# adc_40MHz_v3.net
KiCad netlist of a schematic drawn in EAGLE
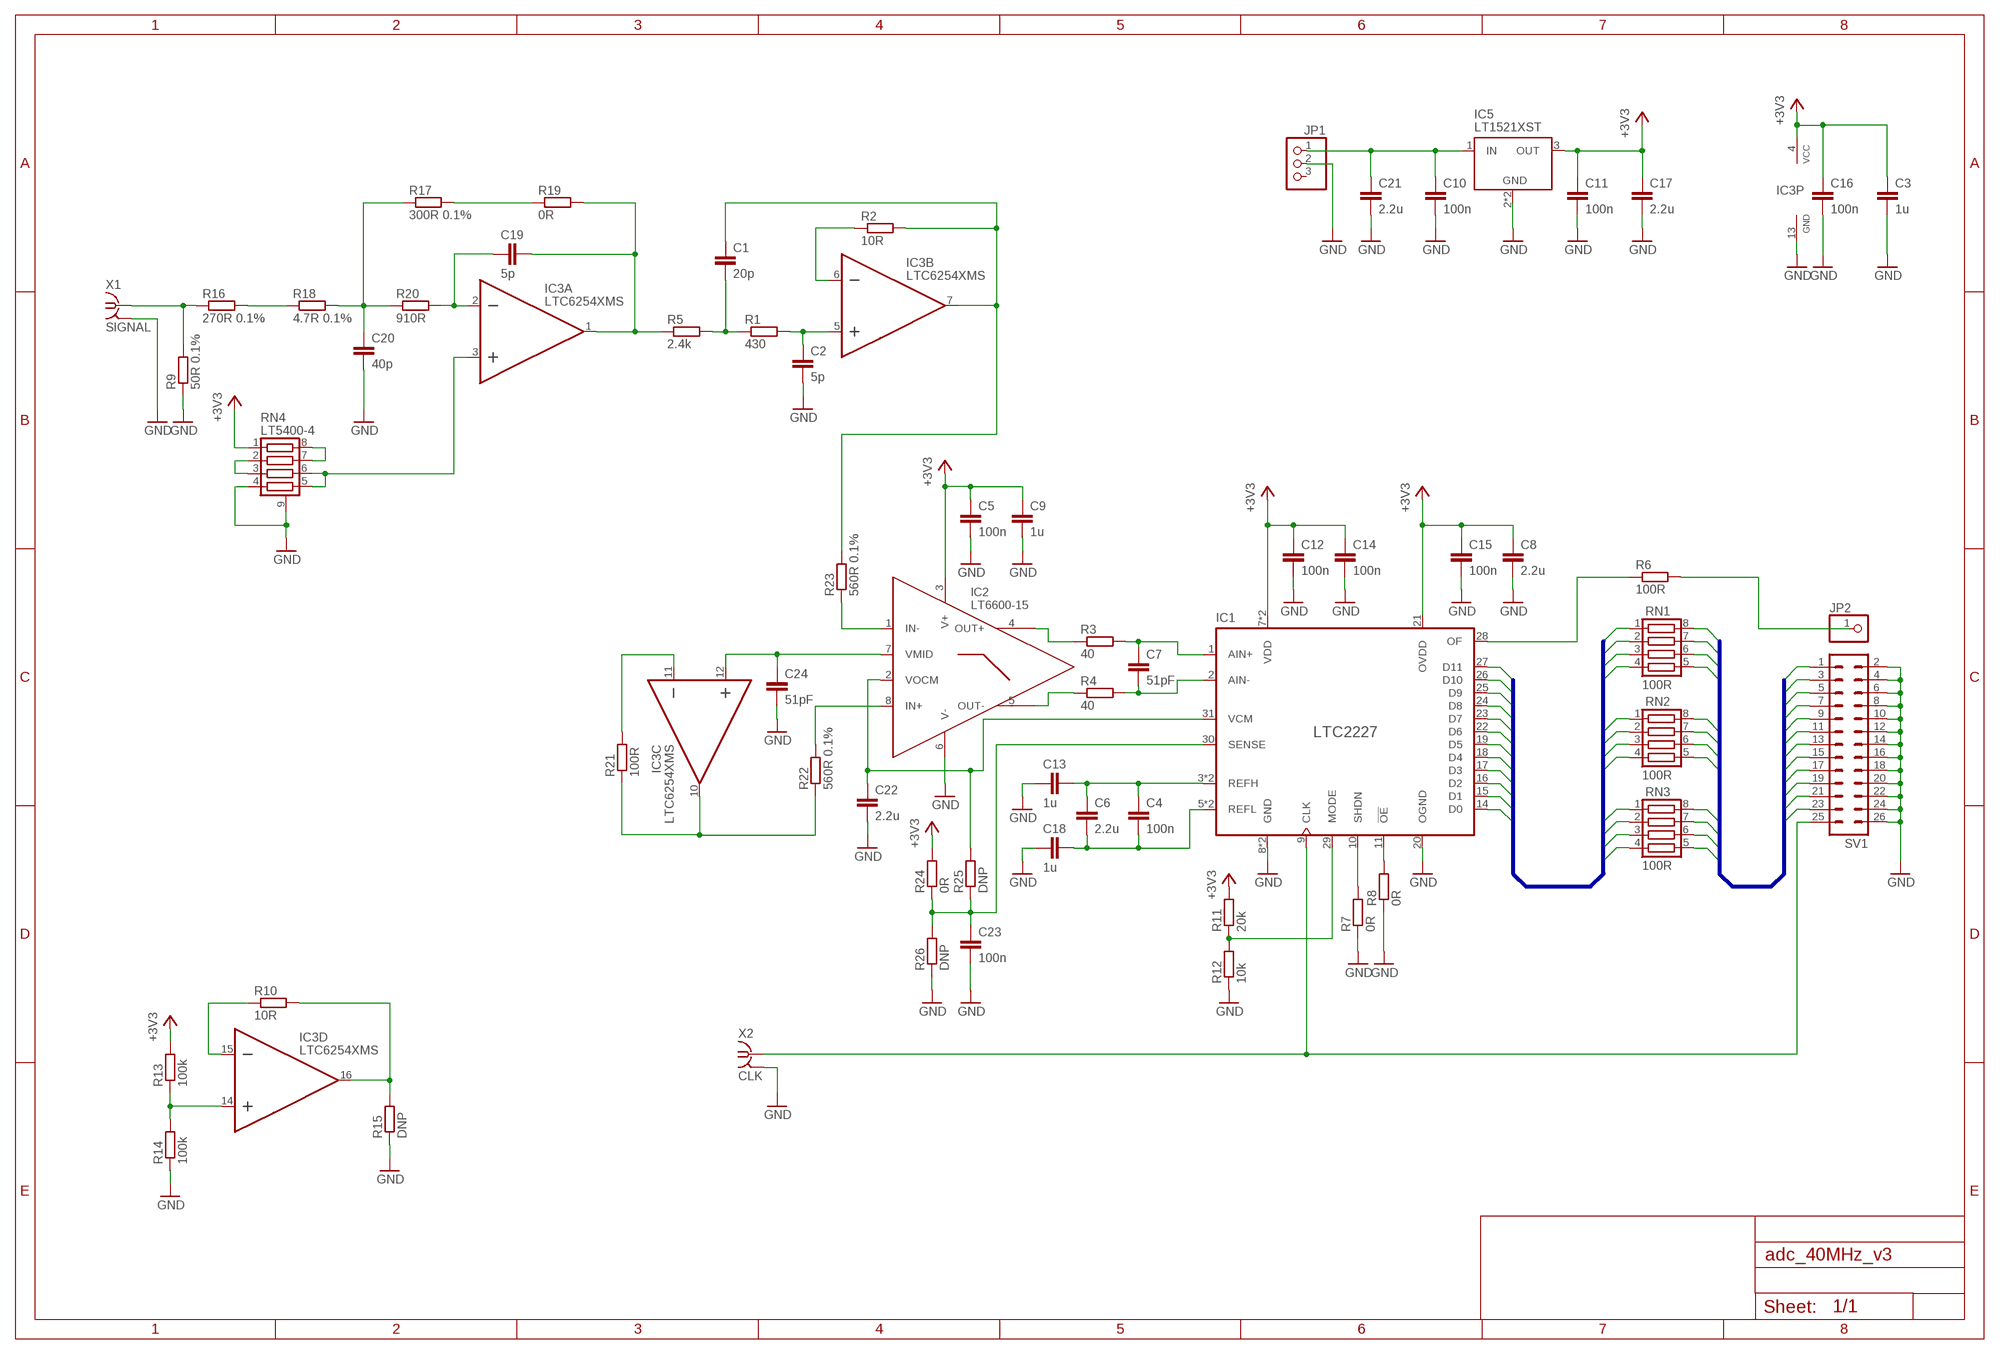
[diagram p0: schematic, sheet 1]

(export (version "E")
  (design (tool "Eeschema 10.0.6"))
  (components
    (comp (ref "C1")
      (value "20p")
      (footprint "eagle-import:C0603")
      (libsource (lib "eagle-import") (part "C-EUC0603"))
    )
    (comp (ref "C2")
      (value "5p")
      (footprint "eagle-import:C0603")
      (libsource (lib "eagle-import") (part "C-EUC0603"))
    )
    (comp (ref "C3")
      (value "1u")
      (footprint "eagle-import:C0805")
      (libsource (lib "eagle-import") (part "C-EUC0805"))
    )
    (comp (ref "C4")
      (value "100n")
      (footprint "eagle-import:C0603")
      (libsource (lib "eagle-import") (part "C-EUC0603"))
    )
    (comp (ref "C5")
      (value "100n")
      (footprint "eagle-import:C0603")
      (libsource (lib "eagle-import") (part "C-EUC0603"))
    )
    (comp (ref "C6")
      (value "2.2u")
      (footprint "eagle-import:C0805")
      (libsource (lib "eagle-import") (part "C-EUC0805"))
    )
    (comp (ref "C7")
      (value "51pF")
      (footprint "eagle-import:C0603")
      (libsource (lib "eagle-import") (part "C-EUC0603"))
    )
    (comp (ref "C8")
      (value "2.2u")
      (footprint "eagle-import:C0805")
      (libsource (lib "eagle-import") (part "C-EUC0805"))
    )
    (comp (ref "C9")
      (value "1u")
      (footprint "eagle-import:C0805")
      (libsource (lib "eagle-import") (part "C-EUC0805"))
    )
    (comp (ref "C10")
      (value "100n")
      (footprint "eagle-import:C0805")
      (libsource (lib "eagle-import") (part "C-EUC0805"))
    )
    (comp (ref "C11")
      (value "100n")
      (footprint "eagle-import:C0805")
      (libsource (lib "eagle-import") (part "C-EUC0805"))
    )
    (comp (ref "C12")
      (value "100n")
      (footprint "eagle-import:C0603")
      (libsource (lib "eagle-import") (part "C-EUC0603"))
    )
    (comp (ref "C13")
      (value "1u")
      (footprint "eagle-import:C0805")
      (libsource (lib "eagle-import") (part "C-EUC0805"))
    )
    (comp (ref "C14")
      (value "100n")
      (footprint "eagle-import:C0603")
      (libsource (lib "eagle-import") (part "C-EUC0603"))
    )
    (comp (ref "C15")
      (value "100n")
      (footprint "eagle-import:C0603")
      (libsource (lib "eagle-import") (part "C-EUC0603"))
    )
    (comp (ref "C16")
      (value "100n")
      (footprint "eagle-import:C0805")
      (libsource (lib "eagle-import") (part "C-EUC0805"))
    )
    (comp (ref "C17")
      (value "2.2u")
      (footprint "eagle-import:C0805")
      (libsource (lib "eagle-import") (part "C-EUC0805"))
    )
    (comp (ref "C18")
      (value "1u")
      (footprint "eagle-import:C0805")
      (libsource (lib "eagle-import") (part "C-EUC0805"))
    )
    (comp (ref "C19")
      (value "5p")
      (footprint "eagle-import:C0603")
      (libsource (lib "eagle-import") (part "C-EUC0603"))
    )
    (comp (ref "C20")
      (value "40p")
      (footprint "eagle-import:C0603")
      (libsource (lib "eagle-import") (part "C-EUC0603"))
    )
    (comp (ref "C21")
      (value "2.2u")
      (footprint "eagle-import:C0805")
      (libsource (lib "eagle-import") (part "C-EUC0805"))
    )
    (comp (ref "C22")
      (value "2.2u")
      (footprint "eagle-import:C0805")
      (libsource (lib "eagle-import") (part "C-EUC0805"))
    )
    (comp (ref "C23")
      (value "100n")
      (footprint "eagle-import:C0603")
      (libsource (lib "eagle-import") (part "C-EUC0603"))
    )
    (comp (ref "C24")
      (value "51pF")
      (footprint "eagle-import:C0603")
      (libsource (lib "eagle-import") (part "C-EUC0603"))
    )
    (comp (ref "IC1")
      (value "LTC2227")
      (footprint "eagle-import:QFN32")
      (libsource (lib "eagle-import") (part "LTC2227"))
    )
    (comp (ref "IC2")
      (value "LT6600-15")
      (footprint "eagle-import:S8")
      (libsource (lib "eagle-import") (part "LT6600-15"))
    )
    (comp (ref "IC3")
      (value "LTC6254XMS")
      (footprint "eagle-import:MSOP16")
      (libsource (lib "eagle-import") (part "LTC6254XMS"))
    )
    (comp (ref "IC5")
      (value "LT1521XST")
      (footprint "eagle-import:SOT223")
      (libsource (lib "eagle-import") (part "LT1521XST"))
    )
    (comp (ref "JP1")
      (value "PINHD-1X3/90")
      (footprint "eagle-import:1X03_90")
      (libsource (lib "eagle-import") (part "PINHD-1X3/90"))
    )
    (comp (ref "JP2")
      (value "PINHD-1X1")
      (footprint "eagle-import:1X01")
      (libsource (lib "eagle-import") (part "PINHD-1X1"))
    )
    (comp (ref "R1")
      (value "430")
      (footprint "eagle-import:R0603")
      (libsource (lib "eagle-import") (part "R-EU_R0603"))
    )
    (comp (ref "R2")
      (value "10R")
      (footprint "eagle-import:R0603")
      (libsource (lib "eagle-import") (part "R-EU_R0603"))
    )
    (comp (ref "R3")
      (value "40")
      (footprint "eagle-import:R0603")
      (libsource (lib "eagle-import") (part "R-EU_R0603"))
    )
    (comp (ref "R4")
      (value "40")
      (footprint "eagle-import:R0603")
      (libsource (lib "eagle-import") (part "R-EU_R0603"))
    )
    (comp (ref "R5")
      (value "2.4k")
      (footprint "eagle-import:R0603")
      (libsource (lib "eagle-import") (part "R-EU_R0603"))
    )
    (comp (ref "R6")
      (value "100R")
      (footprint "eagle-import:R0603")
      (libsource (lib "eagle-import") (part "R-EU_R0603"))
    )
    (comp (ref "R7")
      (value "0R")
      (footprint "eagle-import:R0603")
      (libsource (lib "eagle-import") (part "R-EU_R0603"))
    )
    (comp (ref "R8")
      (value "0R")
      (footprint "eagle-import:R0603")
      (libsource (lib "eagle-import") (part "R-EU_R0603"))
    )
    (comp (ref "R9")
      (value "50R 0.1%")
      (footprint "eagle-import:R0603")
      (libsource (lib "eagle-import") (part "R-EU_R0603"))
    )
    (comp (ref "R10")
      (value "10R")
      (footprint "eagle-import:R0603")
      (libsource (lib "eagle-import") (part "R-EU_R0603"))
    )
    (comp (ref "R11")
      (value "20k")
      (footprint "eagle-import:R0603")
      (libsource (lib "eagle-import") (part "R-EU_R0603"))
    )
    (comp (ref "R12")
      (value "10k")
      (footprint "eagle-import:R0603")
      (libsource (lib "eagle-import") (part "R-EU_R0603"))
    )
    (comp (ref "R13")
      (value "100k")
      (footprint "eagle-import:R0603")
      (libsource (lib "eagle-import") (part "R-EU_R0603"))
    )
    (comp (ref "R14")
      (value "100k")
      (footprint "eagle-import:R0603")
      (libsource (lib "eagle-import") (part "R-EU_R0603"))
    )
    (comp (ref "R15")
      (value "DNP")
      (footprint "eagle-import:R0603")
      (libsource (lib "eagle-import") (part "R-EU_R0603"))
    )
    (comp (ref "R16")
      (value "270R 0.1%")
      (footprint "eagle-import:R0603")
      (libsource (lib "eagle-import") (part "R-EU_R0603"))
    )
    (comp (ref "R17")
      (value "300R 0.1%")
      (footprint "eagle-import:R0603")
      (libsource (lib "eagle-import") (part "R-EU_R0603"))
    )
    (comp (ref "R18")
      (value "4.7R 0.1%")
      (footprint "eagle-import:R0603")
      (libsource (lib "eagle-import") (part "R-EU_R0603"))
    )
    (comp (ref "R19")
      (value "0R")
      (footprint "eagle-import:R0603")
      (libsource (lib "eagle-import") (part "R-EU_R0603"))
    )
    (comp (ref "R20")
      (value "910R")
      (footprint "eagle-import:R0603")
      (libsource (lib "eagle-import") (part "R-EU_R0603"))
    )
    (comp (ref "R21")
      (value "100R")
      (footprint "eagle-import:R0603")
      (libsource (lib "eagle-import") (part "R-EU_R0603"))
    )
    (comp (ref "R22")
      (value "560R 0.1%")
      (footprint "eagle-import:R0603")
      (libsource (lib "eagle-import") (part "R-EU_R0603"))
    )
    (comp (ref "R23")
      (value "560R 0.1%")
      (footprint "eagle-import:R0603")
      (libsource (lib "eagle-import") (part "R-EU_R0603"))
    )
    (comp (ref "R24")
      (value "0R")
      (footprint "eagle-import:R0603")
      (libsource (lib "eagle-import") (part "R-EU_R0603"))
    )
    (comp (ref "R25")
      (value "DNP")
      (footprint "eagle-import:R0603")
      (libsource (lib "eagle-import") (part "R-EU_R0603"))
    )
    (comp (ref "R26")
      (value "DNP")
      (footprint "eagle-import:R0603")
      (libsource (lib "eagle-import") (part "R-EU_R0603"))
    )
    (comp (ref "RN1")
      (value "100R")
      (footprint "eagle-import:EXB38V")
      (libsource (lib "eagle-import") (part "CTS742C083"))
    )
    (comp (ref "RN2")
      (value "100R")
      (footprint "eagle-import:EXB38V")
      (libsource (lib "eagle-import") (part "CTS742C083"))
    )
    (comp (ref "RN3")
      (value "100R")
      (footprint "eagle-import:EXB38V")
      (libsource (lib "eagle-import") (part "CTS742C083"))
    )
    (comp (ref "RN4")
      (value "LT5400-4")
      (footprint "eagle-import:MS8E")
      (libsource (lib "eagle-import") (part "LT5400"))
    )
    (comp (ref "SV1")
      (value "ML26")
      (footprint "eagle-import:ML26")
      (libsource (lib "eagle-import") (part "ML26"))
    )
    (comp (ref "X1")
      (value "SIGNAL")
      (footprint "eagle-import:BU-SMA-H")
      (libsource (lib "eagle-import") (part "BU-SMA-H"))
    )
    (comp (ref "X2")
      (value "CLK")
      (footprint "eagle-import:BU-SMA-H")
      (libsource (lib "eagle-import") (part "BU-SMA-H"))
    )
  )
  (nets
    (net (code "1") (name "+3V3") (class "Default")
      (node (ref "C11") (pin "1") (pinfunction "1_1") (pintype "passive"))
      (node (ref "C12") (pin "1") (pinfunction "1_1") (pintype "passive"))
      (node (ref "C14") (pin "1") (pinfunction "1_1") (pintype "passive"))
      (node (ref "C15") (pin "1") (pinfunction "1_1") (pintype "passive"))
      (node (ref "C16") (pin "1") (pinfunction "1_1") (pintype "passive"))
      (node (ref "C17") (pin "1") (pinfunction "1_1") (pintype "passive"))
      (node (ref "C3") (pin "1") (pinfunction "1_1") (pintype "passive"))
      (node (ref "C5") (pin "1") (pinfunction "1_1") (pintype "passive"))
      (node (ref "C8") (pin "1") (pinfunction "1_1") (pintype "passive"))
      (node (ref "C9") (pin "1") (pinfunction "1_1") (pintype "passive"))
      (node (ref "IC1") (pin "21") (pinfunction "OVDD_21") (pintype "power_in"))
      (node (ref "IC1") (pin "32") (pinfunction "VDD_32") (pintype "power_in"))
      (node (ref "IC1") (pin "7") (pinfunction "VDD_7") (pintype "power_in"))
      (node (ref "IC2") (pin "3") (pinfunction "V+_3") (pintype "power_in"))
      (node (ref "IC3") (pin "4") (pinfunction "V+_4") (pintype "power_in"))
      (node (ref "IC5") (pin "3") (pinfunction "OUT_3") (pintype "output"))
      (node (ref "R11") (pin "2") (pinfunction "2_2") (pintype "passive"))
      (node (ref "R13") (pin "2") (pinfunction "2_2") (pintype "passive"))
      (node (ref "R24") (pin "2") (pinfunction "2_2") (pintype "passive"))
      (node (ref "RN4") (pin "1") (pinfunction "1_1") (pintype "passive"))
    )
    (net (code "2") (name "/ADC_D0") (class "Default")
      (node (ref "IC1") (pin "14") (pinfunction "D0_14") (pintype "output"))
      (node (ref "RN3") (pin "4") (pinfunction "4_4") (pintype "passive"))
    )
    (net (code "3") (name "/ADC_D1") (class "Default")
      (node (ref "IC1") (pin "15") (pinfunction "D1_15") (pintype "output"))
      (node (ref "RN3") (pin "3") (pinfunction "3_3") (pintype "passive"))
    )
    (net (code "4") (name "/ADC_D2") (class "Default")
      (node (ref "IC1") (pin "16") (pinfunction "D2_16") (pintype "output"))
      (node (ref "RN3") (pin "2") (pinfunction "2_2") (pintype "passive"))
    )
    (net (code "5") (name "/ADC_D3") (class "Default")
      (node (ref "IC1") (pin "17") (pinfunction "D3_17") (pintype "output"))
      (node (ref "RN3") (pin "1") (pinfunction "1_1") (pintype "passive"))
    )
    (net (code "6") (name "/ADC_D4") (class "Default")
      (node (ref "IC1") (pin "18") (pinfunction "D4_18") (pintype "output"))
      (node (ref "RN2") (pin "4") (pinfunction "4_4") (pintype "passive"))
    )
    (net (code "7") (name "/ADC_D5") (class "Default")
      (node (ref "IC1") (pin "19") (pinfunction "D5_19") (pintype "output"))
      (node (ref "RN2") (pin "3") (pinfunction "3_3") (pintype "passive"))
    )
    (net (code "8") (name "/ADC_D6") (class "Default")
      (node (ref "IC1") (pin "22") (pinfunction "D6_22") (pintype "output"))
      (node (ref "RN2") (pin "2") (pinfunction "2_2") (pintype "passive"))
    )
    (net (code "9") (name "/ADC_D7") (class "Default")
      (node (ref "IC1") (pin "23") (pinfunction "D7_23") (pintype "output"))
      (node (ref "RN2") (pin "1") (pinfunction "1_1") (pintype "passive"))
    )
    (net (code "10") (name "/ADC_D8") (class "Default")
      (node (ref "IC1") (pin "24") (pinfunction "D8_24") (pintype "output"))
      (node (ref "RN1") (pin "4") (pinfunction "4_4") (pintype "passive"))
    )
    (net (code "11") (name "/ADC_D9") (class "Default")
      (node (ref "IC1") (pin "25") (pinfunction "D9_25") (pintype "output"))
      (node (ref "RN1") (pin "3") (pinfunction "3_3") (pintype "passive"))
    )
    (net (code "12") (name "/ADC_D10") (class "Default")
      (node (ref "IC1") (pin "26") (pinfunction "D10_26") (pintype "output"))
      (node (ref "RN1") (pin "2") (pinfunction "2_2") (pintype "passive"))
    )
    (net (code "13") (name "/ADC_D11") (class "Default")
      (node (ref "IC1") (pin "27") (pinfunction "D11_27") (pintype "output"))
      (node (ref "RN1") (pin "1") (pinfunction "1_1") (pintype "passive"))
    )
    (net (code "14") (name "/DAC_D0") (class "Default")
      (node (ref "RN3") (pin "5") (pinfunction "5_5") (pintype "passive"))
      (node (ref "SV1") (pin "23") (pinfunction "23_23") (pintype "passive"))
    )
    (net (code "15") (name "/DAC_D1") (class "Default")
      (node (ref "RN3") (pin "6") (pinfunction "6_6") (pintype "passive"))
      (node (ref "SV1") (pin "21") (pinfunction "21_21") (pintype "passive"))
    )
    (net (code "16") (name "/DAC_D2") (class "Default")
      (node (ref "RN3") (pin "7") (pinfunction "7_7") (pintype "passive"))
      (node (ref "SV1") (pin "19") (pinfunction "19_19") (pintype "passive"))
    )
    (net (code "17") (name "/DAC_D3") (class "Default")
      (node (ref "RN3") (pin "8") (pinfunction "8_8") (pintype "passive"))
      (node (ref "SV1") (pin "17") (pinfunction "17_17") (pintype "passive"))
    )
    (net (code "18") (name "/DAC_D4") (class "Default")
      (node (ref "RN2") (pin "5") (pinfunction "5_5") (pintype "passive"))
      (node (ref "SV1") (pin "15") (pinfunction "15_15") (pintype "passive"))
    )
    (net (code "19") (name "/DAC_D5") (class "Default")
      (node (ref "RN2") (pin "6") (pinfunction "6_6") (pintype "passive"))
      (node (ref "SV1") (pin "13") (pinfunction "13_13") (pintype "passive"))
    )
    (net (code "20") (name "/DAC_D6") (class "Default")
      (node (ref "RN2") (pin "7") (pinfunction "7_7") (pintype "passive"))
      (node (ref "SV1") (pin "11") (pinfunction "11_11") (pintype "passive"))
    )
    (net (code "21") (name "/DAC_D7") (class "Default")
      (node (ref "RN2") (pin "8") (pinfunction "8_8") (pintype "passive"))
      (node (ref "SV1") (pin "9") (pinfunction "9_9") (pintype "passive"))
    )
    (net (code "22") (name "/DAC_D8") (class "Default")
      (node (ref "RN1") (pin "5") (pinfunction "5_5") (pintype "passive"))
      (node (ref "SV1") (pin "7") (pinfunction "7_7") (pintype "passive"))
    )
    (net (code "23") (name "/DAC_D9") (class "Default")
      (node (ref "RN1") (pin "6") (pinfunction "6_6") (pintype "passive"))
      (node (ref "SV1") (pin "5") (pinfunction "5_5") (pintype "passive"))
    )
    (net (code "24") (name "/DAC_D10") (class "Default")
      (node (ref "RN1") (pin "7") (pinfunction "7_7") (pintype "passive"))
      (node (ref "SV1") (pin "3") (pinfunction "3_3") (pintype "passive"))
    )
    (net (code "25") (name "/DAC_D11") (class "Default")
      (node (ref "RN1") (pin "8") (pinfunction "8_8") (pintype "passive"))
      (node (ref "SV1") (pin "1") (pinfunction "1_1") (pintype "passive"))
    )
    (net (code "26") (name "GND") (class "Default")
      (node (ref "C10") (pin "2") (pinfunction "2_2") (pintype "passive"))
      (node (ref "C11") (pin "2") (pinfunction "2_2") (pintype "passive"))
      (node (ref "C12") (pin "2") (pinfunction "2_2") (pintype "passive"))
      (node (ref "C13") (pin "1") (pinfunction "1_1") (pintype "passive"))
      (node (ref "C14") (pin "2") (pinfunction "2_2") (pintype "passive"))
      (node (ref "C15") (pin "2") (pinfunction "2_2") (pintype "passive"))
      (node (ref "C16") (pin "2") (pinfunction "2_2") (pintype "passive"))
      (node (ref "C17") (pin "2") (pinfunction "2_2") (pintype "passive"))
      (node (ref "C18") (pin "1") (pinfunction "1_1") (pintype "passive"))
      (node (ref "C2") (pin "2") (pinfunction "2_2") (pintype "passive"))
      (node (ref "C20") (pin "2") (pinfunction "2_2") (pintype "passive"))
      (node (ref "C21") (pin "2") (pinfunction "2_2") (pintype "passive"))
      (node (ref "C22") (pin "2") (pinfunction "2_2") (pintype "passive"))
      (node (ref "C23") (pin "2") (pinfunction "2_2") (pintype "passive"))
      (node (ref "C24") (pin "2") (pinfunction "2_2") (pintype "passive"))
      (node (ref "C3") (pin "2") (pinfunction "2_2") (pintype "passive"))
      (node (ref "C5") (pin "2") (pinfunction "2_2") (pintype "passive"))
      (node (ref "C8") (pin "2") (pinfunction "2_2") (pintype "passive"))
      (node (ref "C9") (pin "2") (pinfunction "2_2") (pintype "passive"))
      (node (ref "IC1") (pin "20") (pinfunction "OGND_20") (pintype "power_in"))
      (node (ref "IC1") (pin "33") (pinfunction "GND_33") (pintype "power_in"))
      (node (ref "IC1") (pin "8") (pinfunction "GND_8") (pintype "power_in"))
      (node (ref "IC2") (pin "6") (pinfunction "V-_6") (pintype "power_in"))
      (node (ref "IC3") (pin "13") (pinfunction "V-_13") (pintype "power_in"))
      (node (ref "IC5") (pin "2") (pinfunction "GND_2") (pintype "power_in"))
      (node (ref "IC5") (pin "4") (pinfunction "GND_4") (pintype "power_in"))
      (node (ref "JP1") (pin "2") (pinfunction "2_2") (pintype "passive"))
      (node (ref "R12") (pin "1") (pinfunction "1_1") (pintype "passive"))
      (node (ref "R14") (pin "1") (pinfunction "1_1") (pintype "passive"))
      (node (ref "R15") (pin "1") (pinfunction "1_1") (pintype "passive"))
      (node (ref "R26") (pin "1") (pinfunction "1_1") (pintype "passive"))
      (node (ref "R7") (pin "1") (pinfunction "1_1") (pintype "passive"))
      (node (ref "R8") (pin "1") (pinfunction "1_1") (pintype "passive"))
      (node (ref "R9") (pin "1") (pinfunction "1_1") (pintype "passive"))
      (node (ref "RN4") (pin "4") (pinfunction "4_4") (pintype "passive"))
      (node (ref "RN4") (pin "9") (pinfunction "EP_9") (pintype "power_in"))
      (node (ref "SV1") (pin "10") (pinfunction "10_10") (pintype "passive"))
      (node (ref "SV1") (pin "12") (pinfunction "12_12") (pintype "passive"))
      (node (ref "SV1") (pin "14") (pinfunction "14_14") (pintype "passive"))
      (node (ref "SV1") (pin "16") (pinfunction "16_16") (pintype "passive"))
      (node (ref "SV1") (pin "18") (pinfunction "18_18") (pintype "passive"))
      (node (ref "SV1") (pin "2") (pinfunction "2_2") (pintype "passive"))
      (node (ref "SV1") (pin "20") (pinfunction "20_20") (pintype "passive"))
      (node (ref "SV1") (pin "22") (pinfunction "22_22") (pintype "passive"))
      (node (ref "SV1") (pin "24") (pinfunction "24_24") (pintype "passive"))
      (node (ref "SV1") (pin "26") (pinfunction "26_26") (pintype "passive"))
      (node (ref "SV1") (pin "4") (pinfunction "4_4") (pintype "passive"))
      (node (ref "SV1") (pin "6") (pinfunction "6_6") (pintype "passive"))
      (node (ref "SV1") (pin "8") (pinfunction "8_8") (pintype "passive"))
      (node (ref "X1") (pin "2") (pinfunction "2_2") (pintype "passive"))
      (node (ref "X1") (pin "3") (pinfunction "2_3") (pintype "passive"))
      (node (ref "X1") (pin "4") (pinfunction "2_4") (pintype "passive"))
      (node (ref "X1") (pin "5") (pinfunction "2_5") (pintype "passive"))
      (node (ref "X2") (pin "2") (pinfunction "2_2") (pintype "passive"))
      (node (ref "X2") (pin "3") (pinfunction "2_3") (pintype "passive"))
      (node (ref "X2") (pin "4") (pinfunction "2_4") (pintype "passive"))
      (node (ref "X2") (pin "5") (pinfunction "2_5") (pintype "passive"))
    )
    (net (code "27") (name "Net-(C1-Pad2)") (class "Default")
      (node (ref "C1") (pin "2") (pinfunction "2_2") (pintype "passive"))
      (node (ref "R1") (pin "1") (pinfunction "1_1") (pintype "passive"))
      (node (ref "R5") (pin "2") (pinfunction "2_2") (pintype "passive"))
    )
    (net (code "28") (name "Net-(C13-Pad2)") (class "Default")
      (node (ref "C13") (pin "2") (pinfunction "2_2") (pintype "passive"))
      (node (ref "C4") (pin "1") (pinfunction "1_1") (pintype "passive"))
      (node (ref "C6") (pin "1") (pinfunction "1_1") (pintype "passive"))
      (node (ref "IC1") (pin "3") (pinfunction "REFH_3") (pintype "passive"))
      (node (ref "IC1") (pin "4") (pinfunction "REFH_4") (pintype "passive"))
    )
    (net (code "29") (name "Net-(C18-Pad2)") (class "Default")
      (node (ref "C18") (pin "2") (pinfunction "2_2") (pintype "passive"))
      (node (ref "C4") (pin "2") (pinfunction "2_2") (pintype "passive"))
      (node (ref "C6") (pin "2") (pinfunction "2_2") (pintype "passive"))
      (node (ref "IC1") (pin "5") (pinfunction "REFL_5") (pintype "passive"))
      (node (ref "IC1") (pin "6") (pinfunction "REFL_6") (pintype "passive"))
    )
    (net (code "30") (name "Net-(C20-Pad1)") (class "Default")
      (node (ref "C20") (pin "1") (pinfunction "1_1") (pintype "passive"))
      (node (ref "R17") (pin "1") (pinfunction "1_1") (pintype "passive"))
      (node (ref "R18") (pin "2") (pinfunction "2_2") (pintype "passive"))
      (node (ref "R20") (pin "1") (pinfunction "1_1") (pintype "passive"))
    )
    (net (code "31") (name "Net-(IC1-AIN+)") (class "Default")
      (node (ref "C7") (pin "1") (pinfunction "1_1") (pintype "passive"))
      (node (ref "IC1") (pin "1") (pinfunction "AIN+_1") (pintype "input"))
      (node (ref "R3") (pin "2") (pinfunction "2_2") (pintype "passive"))
    )
    (net (code "32") (name "Net-(IC1-AIN-)") (class "Default")
      (node (ref "C7") (pin "2") (pinfunction "2_2") (pintype "passive"))
      (node (ref "IC1") (pin "2") (pinfunction "AIN-_2") (pintype "input"))
      (node (ref "R4") (pin "2") (pinfunction "2_2") (pintype "passive"))
    )
    (net (code "33") (name "Net-(IC1-CLK)") (class "Default")
      (node (ref "IC1") (pin "9") (pinfunction "CLK_9") (pintype "input"))
      (node (ref "SV1") (pin "25") (pinfunction "25_25") (pintype "passive"))
      (node (ref "X2") (pin "1") (pinfunction "1_1") (pintype "passive"))
    )
    (net (code "34") (name "Net-(IC1-MODE)") (class "Default")
      (node (ref "IC1") (pin "29") (pinfunction "MODE_29") (pintype "input"))
      (node (ref "R11") (pin "1") (pinfunction "1_1") (pintype "passive"))
      (node (ref "R12") (pin "2") (pinfunction "2_2") (pintype "passive"))
    )
    (net (code "35") (name "Net-(IC1-OF)") (class "Default")
      (node (ref "IC1") (pin "28") (pinfunction "OF_28") (pintype "output"))
      (node (ref "R6") (pin "1") (pinfunction "1_1") (pintype "passive"))
    )
    (net (code "36") (name "Net-(IC1-SENSE)") (class "Default")
      (node (ref "C23") (pin "1") (pinfunction "1_1") (pintype "passive"))
      (node (ref "IC1") (pin "30") (pinfunction "SENSE_30") (pintype "input"))
      (node (ref "R24") (pin "1") (pinfunction "1_1") (pintype "passive"))
      (node (ref "R25") (pin "1") (pinfunction "1_1") (pintype "passive"))
      (node (ref "R26") (pin "2") (pinfunction "2_2") (pintype "passive"))
    )
    (net (code "37") (name "Net-(IC1-SHDN)") (class "Default")
      (node (ref "IC1") (pin "10") (pinfunction "SHDN_10") (pintype "input"))
      (node (ref "R7") (pin "2") (pinfunction "2_2") (pintype "passive"))
    )
    (net (code "38") (name "Net-(IC1-VCM)") (class "Default")
      (node (ref "C22") (pin "1") (pinfunction "1_1") (pintype "passive"))
      (node (ref "IC1") (pin "31") (pinfunction "VCM_31") (pintype "passive"))
      (node (ref "IC2") (pin "2") (pinfunction "VOCM_2") (pintype "input"))
      (node (ref "R25") (pin "2") (pinfunction "2_2") (pintype "passive"))
    )
    (net (code "39") (name "Net-(IC1-~{OE})") (class "Default")
      (node (ref "IC1") (pin "11") (pinfunction "~{OE}_11") (pintype "input"))
      (node (ref "R8") (pin "2") (pinfunction "2_2") (pintype "passive"))
    )
    (net (code "40") (name "Net-(IC2-IN+)") (class "Default")
      (node (ref "IC2") (pin "8") (pinfunction "IN+_8") (pintype "input"))
      (node (ref "R22") (pin "2") (pinfunction "2_2") (pintype "passive"))
    )
    (net (code "41") (name "Net-(IC2-IN-)") (class "Default")
      (node (ref "IC2") (pin "1") (pinfunction "IN-_1") (pintype "input"))
      (node (ref "R23") (pin "1") (pinfunction "1_1") (pintype "passive"))
    )
    (net (code "42") (name "Net-(IC2-OUT+)") (class "Default")
      (node (ref "IC2") (pin "4") (pinfunction "OUT+_4") (pintype "output"))
      (node (ref "R3") (pin "1") (pinfunction "1_1") (pintype "passive"))
    )
    (net (code "43") (name "Net-(IC2-OUT-)") (class "Default")
      (node (ref "IC2") (pin "5") (pinfunction "OUT-_5") (pintype "output"))
      (node (ref "R4") (pin "1") (pinfunction "1_1") (pintype "passive"))
    )
    (net (code "44") (name "Net-(IC2-VMID)") (class "Default")
      (node (ref "C24") (pin "1") (pinfunction "1_1") (pintype "passive"))
      (node (ref "IC2") (pin "7") (pinfunction "VMID_7") (pintype "input"))
      (node (ref "IC3") (pin "12") (pinfunction "+IN_12") (pintype "input"))
    )
    (net (code "45") (name "Net-(IC3A-+IN)") (class "Default")
      (node (ref "IC3") (pin "3") (pinfunction "+IN_3") (pintype "input"))
      (node (ref "RN4") (pin "5") (pinfunction "5_5") (pintype "passive"))
      (node (ref "RN4") (pin "6") (pinfunction "6_6") (pintype "passive"))
    )
    (net (code "46") (name "Net-(IC3A--IN)") (class "Default")
      (node (ref "C19") (pin "1") (pinfunction "1_1") (pintype "passive"))
      (node (ref "IC3") (pin "2") (pinfunction "-IN_2") (pintype "input"))
      (node (ref "R20") (pin "2") (pinfunction "2_2") (pintype "passive"))
    )
    (net (code "47") (name "Net-(IC3A-OUT)") (class "Default")
      (node (ref "C19") (pin "2") (pinfunction "2_2") (pintype "passive"))
      (node (ref "IC3") (pin "1") (pinfunction "OUT_1") (pintype "output"))
      (node (ref "R19") (pin "2") (pinfunction "2_2") (pintype "passive"))
      (node (ref "R5") (pin "1") (pinfunction "1_1") (pintype "passive"))
    )
    (net (code "48") (name "Net-(IC3B-+IN)") (class "Default")
      (node (ref "C2") (pin "1") (pinfunction "1_1") (pintype "passive"))
      (node (ref "IC3") (pin "5") (pinfunction "+IN_5") (pintype "input"))
      (node (ref "R1") (pin "2") (pinfunction "2_2") (pintype "passive"))
    )
    (net (code "49") (name "Net-(IC3B--IN)") (class "Default")
      (node (ref "IC3") (pin "6") (pinfunction "-IN_6") (pintype "input"))
      (node (ref "R2") (pin "1") (pinfunction "1_1") (pintype "passive"))
    )
    (net (code "50") (name "Net-(IC3B-OUT)") (class "Default")
      (node (ref "C1") (pin "1") (pinfunction "1_1") (pintype "passive"))
      (node (ref "IC3") (pin "7") (pinfunction "OUT_7") (pintype "output"))
      (node (ref "R2") (pin "2") (pinfunction "2_2") (pintype "passive"))
      (node (ref "R23") (pin "2") (pinfunction "2_2") (pintype "passive"))
    )
    (net (code "51") (name "Net-(IC3C--IN)") (class "Default")
      (node (ref "IC3") (pin "11") (pinfunction "-IN_11") (pintype "input"))
      (node (ref "R21") (pin "2") (pinfunction "2_2") (pintype "passive"))
    )
    (net (code "52") (name "Net-(IC3C-OUT)") (class "Default")
      (node (ref "IC3") (pin "10") (pinfunction "OUT_10") (pintype "output"))
      (node (ref "R21") (pin "1") (pinfunction "1_1") (pintype "passive"))
      (node (ref "R22") (pin "1") (pinfunction "1_1") (pintype "passive"))
    )
    (net (code "53") (name "Net-(IC3D-+IN)") (class "Default")
      (node (ref "IC3") (pin "14") (pinfunction "+IN_14") (pintype "input"))
      (node (ref "R13") (pin "1") (pinfunction "1_1") (pintype "passive"))
      (node (ref "R14") (pin "2") (pinfunction "2_2") (pintype "passive"))
    )
    (net (code "54") (name "Net-(IC3D--IN)") (class "Default")
      (node (ref "IC3") (pin "15") (pinfunction "-IN_15") (pintype "input"))
      (node (ref "R10") (pin "1") (pinfunction "1_1") (pintype "passive"))
    )
    (net (code "55") (name "Net-(IC3D-OUT)") (class "Default")
      (node (ref "IC3") (pin "16") (pinfunction "OUT_16") (pintype "output"))
      (node (ref "R10") (pin "2") (pinfunction "2_2") (pintype "passive"))
      (node (ref "R15") (pin "2") (pinfunction "2_2") (pintype "passive"))
    )
    (net (code "56") (name "Net-(IC5-IN)") (class "Default")
      (node (ref "C10") (pin "1") (pinfunction "1_1") (pintype "passive"))
      (node (ref "C21") (pin "1") (pinfunction "1_1") (pintype "passive"))
      (node (ref "IC5") (pin "1") (pinfunction "IN_1") (pintype "input"))
      (node (ref "JP1") (pin "1") (pinfunction "1_1") (pintype "passive"))
    )
    (net (code "57") (name "Net-(JP2-Pad1)") (class "Default")
      (node (ref "JP2") (pin "1") (pinfunction "1_1") (pintype "passive"))
      (node (ref "R6") (pin "2") (pinfunction "2_2") (pintype "passive"))
    )
    (net (code "58") (name "Net-(R16-Pad1)") (class "Default")
      (node (ref "R16") (pin "1") (pinfunction "1_1") (pintype "passive"))
      (node (ref "R9") (pin "2") (pinfunction "2_2") (pintype "passive"))
      (node (ref "X1") (pin "1") (pinfunction "1_1") (pintype "passive"))
    )
    (net (code "59") (name "Net-(R16-Pad2)") (class "Default")
      (node (ref "R16") (pin "2") (pinfunction "2_2") (pintype "passive"))
      (node (ref "R18") (pin "1") (pinfunction "1_1") (pintype "passive"))
    )
    (net (code "60") (name "Net-(R17-Pad2)") (class "Default")
      (node (ref "R17") (pin "2") (pinfunction "2_2") (pintype "passive"))
      (node (ref "R19") (pin "1") (pinfunction "1_1") (pintype "passive"))
    )
    (net (code "61") (name "Net-(RN4-Pad2)") (class "Default")
      (node (ref "RN4") (pin "2") (pinfunction "2_2") (pintype "passive"))
      (node (ref "RN4") (pin "3") (pinfunction "3_3") (pintype "passive"))
    )
    (net (code "62") (name "Net-(RN4-Pad7)") (class "Default")
      (node (ref "RN4") (pin "7") (pinfunction "7_7") (pintype "passive"))
      (node (ref "RN4") (pin "8") (pinfunction "8_8") (pintype "passive"))
    )
    (net (code "63") (name "unconnected-(JP1-Pad3)") (class "Default")
      (node (ref "JP1") (pin "3") (pinfunction "3_3") (pintype "passive"))
    )
  )
)
